# PG14__POWER_CONTROL.net
KiCad netlist of a schematic drawn in Altium Designer
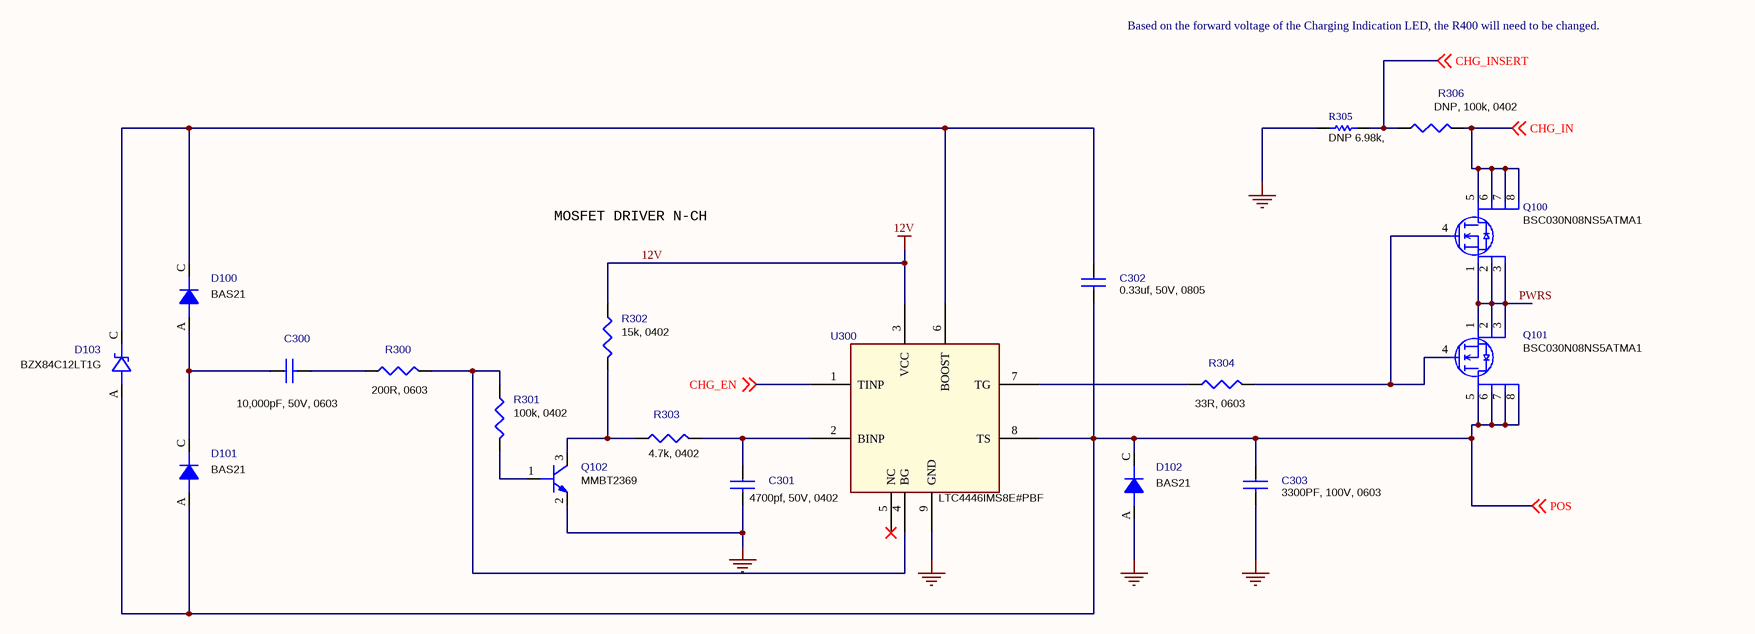
[diagram p0: PG14_ POWER CONTROL.SchDoc]

(export (version "E")
  (design (tool "Eeschema 10.0.6"))
  (components
    (comp (ref "C300")
      (value "10,000pF, 50V, 0603")
      (footprint "C0603")
      (description "CAP CER 10000PF 50V X7R 0603")
      (fields
        (field (name "MANUFACTURER") "TDK")
        (field (name "MANUFACTURER PART NUMBER") "CGA3E2X7R1H103K080AE")
      )
      (libsource (lib "*") (part "CAP-Generic-0603"))
    )
    (comp (ref "C301")
      (value "4700pf, 50V, 0402")
      (footprint "C0402")
      (description "CAP CER 4700PF 50V X7R 0402")
      (fields
        (field (name "MANUFACTURER") "TDK")
        (field (name "MANUFACTURER PART NUMBER") "CGA2B2X7R1H472K050BE")
      )
      (libsource (lib "*") (part "CAP-Generic-0402"))
    )
    (comp (ref "C302")
      (value "0.33uf, 50V, 0805")
      (footprint "C0805")
      (description "CAP CER 0.33UF 50V X7R 0805")
      (fields
        (field (name "MANUFACTURER") "KEMET")
        (field (name "MANUFACTURER PART NUMBER") "C0805X334K5RACAUTO")
      )
      (libsource (lib "*") (part "CAP-Generic-0603"))
    )
    (comp (ref "C303")
      (value "3300PF, 100V, 0603")
      (footprint "C0603")
      (description "CAP CER 3300PF 100V X7R 0603")
      (fields
        (field (name "MANUFACTURER") "Murata")
        (field (name "MANUFACTURER PART NUMBER") "GCJ188R72A332KA01D")
      )
      (libsource (lib "*") (part "CAP-Generic-0402"))
    )
    (comp (ref "D100")
      (value "BAS21")
      (footprint "BAS21")
      (description "DIODE GEN PURP 250V 200MA SOT23")
      (fields (field (name "MANUFACTURER") "Vishay") (field (name "MANUFACTURER PART NUMBER") "BAS21-HE3-08"))
      (libsource (lib "*") (part "DIO-GENERIC"))
    )
    (comp (ref "D101")
      (value "BAS21")
      (footprint "BAS21")
      (description "DIODE GEN PURP 250V 200MA SOT23")
      (fields (field (name "MANUFACTURER") "Vishay") (field (name "MANUFACTURER PART NUMBER") "BAS21-HE3-08"))
      (libsource (lib "*") (part "DIO-GENERIC"))
    )
    (comp (ref "D102")
      (value "BAS21")
      (footprint "BAS21")
      (description "DIODE GEN PURP 250V 200MA SOT23")
      (fields (field (name "MANUFACTURER") "Vishay") (field (name "MANUFACTURER PART NUMBER") "BAS21-HE3-08"))
      (libsource (lib "*") (part "DIO-GENERIC"))
    )
    (comp (ref "D103")
      (value "BZX84C12LT1G")
      (footprint "SOT23-3")
      (description "DIODE ZENER 12V 225MW SOT23-3")
      (fields (field (name "MANUFACTURER") "ON Semiconductor") (field (name "TOLERANCE") "5%"))
      (libsource (lib "*") (part "DIO-ZENER-GENERIC"))
    )
    (comp (ref "Q100")
      (value "BSC030N08NS5ATMA1")
      (footprint "8TDSON")
      (description "MOSFET N-CH 80V 100A 8TDSON")
      (fields (field (name "MANUFACTURER") "Infineon"))
      (libsource (lib "M2_V8_BMU_V1.0") (part "BSC030N08NS5ATMA1"))
    )
    (comp (ref "Q101")
      (value "BSC030N08NS5ATMA1")
      (footprint "8TDSON")
      (description "MOSFET N-CH 80V 100A 8TDSON")
      (fields (field (name "MANUFACTURER") "Infineon"))
      (libsource (lib "M2_V8_BMU_V1.0") (part "BSC030N08NS5ATMA1"))
    )
    (comp (ref "Q102")
      (value "MMBT2369")
      (footprint "SOT-23-3")
      (description "TRANS NPN 15V 0.2A SOT-23")
      (fields
        (field (name "MANUFACTURER") "ON Semiconductor / Fairchild")
        (field (name "MANUFACTURER PART NUMBER") "MMBT2369A")
      )
      (libsource (lib "*") (part "Trans-Generic_4"))
    )
    (comp (ref "R300")
      (value "200R, 0603")
      (footprint "R0603")
      (description "RES SMD 200 OHM 1% 1/10W 0603")
      (fields
        (field (name "MANUFACTURER") "Yageo")
        (field (name "MANUFACTURER PART NUMBER") "AC0603FR-07200RL")
      )
      (libsource (lib "*") (part "R-Generic-0603"))
    )
    (comp (ref "R301")
      (value "100k, 0402")
      (footprint "R0402")
      (description "RES SMD 100K OHM 1% 1/16W 0402")
      (fields
        (field (name "MANUFACTURER") "Yageo")
        (field (name "MANUFACTURER PART NUMBER") "RC0402FR-07100KL")
      )
      (libsource (lib "*") (part "R-Generic-0402"))
    )
    (comp (ref "R302")
      (value "15k, 0402")
      (footprint "R0402")
      (description "RES SMD 15K OHM 1% 1/16W 0402")
      (fields
        (field (name "MANUFACTURER") "Yageo")
        (field (name "MANUFACTURER PART NUMBER") "RC0402FR-0715KL")
      )
      (libsource (lib "*") (part "R-Generic-0402"))
    )
    (comp (ref "R303")
      (value "4.7k, 0402")
      (footprint "R0402")
      (description "RES SMD 4.7K OHM 1% 1/16W 0402")
      (fields
        (field (name "MANUFACTURER") "Yageo")
        (field (name "MANUFACTURER PART NUMBER") "RC0402FR-074K7L")
      )
      (libsource (lib "*") (part "R-Generic-0402"))
    )
    (comp (ref "R304")
      (value "33R, 0603")
      (footprint "R0603")
      (description "RES SMD 33 OHM 1% 1/10W 0603")
      (fields
        (field (name "MANUFACTURER") "Yageo")
        (field (name "MANUFACTURER PART NUMBER") "AC0603FR-0733RL")
      )
      (libsource (lib "*") (part "R-Generic-0603"))
    )
    (comp (ref "R305")
      (value "DNP 6.98k,")
      (footprint "R0402")
      (description "Resistor")
      (fields (field (name "PUBLISHER") "Altium Limited"))
      (libsource (lib "Miscellaneous Devices") (part "Res1"))
    )
    (comp (ref "R306")
      (value "DNP, 100k, 0402")
      (footprint "R0402")
      (description "RES SMD 100K OHM 1% 1/16W 0402")
      (fields
        (field (name "MANUFACTURER") "Yageo")
        (field (name "MANUFACTURER PART NUMBER") "RC0402FR-07100KL")
      )
      (libsource (lib "*") (part "R-Generic-0402"))
    )
    (comp (ref "U300")
      (value "LTC4446IMS8E#PBF")
      (footprint "8-MSOP")
      (description "IC MOSFET DRIVER N-CH 8-MSOP")
      (fields
        (field (name "MANUFACTURER") "Analog Devices / Linear Technology")
        (field (name "TOLERANCE") "10%")
      )
      (libsource (lib "*") (part "IC-LTC4446IMS8EPBF-700-510"))
    )
  )
  (nets
    (net (code "1") (name "/PWRS") (class "Default")
      (node (ref "Q100") (pin "1") (pinfunction "S1_1") (pintype "bidirectional"))
      (node (ref "Q100") (pin "2") (pinfunction "S2_2") (pintype "bidirectional"))
      (node (ref "Q100") (pin "3") (pinfunction "S3_3") (pintype "bidirectional"))
      (node (ref "Q101") (pin "1") (pinfunction "S1_1") (pintype "bidirectional"))
      (node (ref "Q101") (pin "2") (pinfunction "S2_2") (pintype "bidirectional"))
      (node (ref "Q101") (pin "3") (pinfunction "S3_3") (pintype "bidirectional"))
    )
    (net (code "2") (name "12V") (class "Default")
      (node (ref "R302") (pin "1") (pinfunction "1_1") (pintype "passive"))
      (node (ref "U300") (pin "3") (pinfunction "VCC_3") (pintype "passive"))
    )
    (net (code "3") (name "CHG_EN") (class "Default")
      (node (ref "U300") (pin "1") (pinfunction "TINP_1") (pintype "passive"))
    )
    (net (code "4") (name "CHG_IN") (class "Default")
      (node (ref "Q100") (pin "5") (pinfunction "D1_5") (pintype "bidirectional"))
      (node (ref "Q100") (pin "6") (pinfunction "D2_6") (pintype "bidirectional"))
      (node (ref "Q100") (pin "7") (pinfunction "D3_7") (pintype "bidirectional"))
      (node (ref "Q100") (pin "8") (pinfunction "D4_8") (pintype "bidirectional"))
      (node (ref "R306") (pin "2") (pinfunction "2_2") (pintype "passive"))
    )
    (net (code "5") (name "CHG_INSERT") (class "Default")
      (node (ref "R305") (pin "2") (pinfunction "2_2") (pintype "passive"))
      (node (ref "R306") (pin "1") (pinfunction "1_1") (pintype "passive"))
    )
    (net (code "6") (name "GND") (class "Default")
      (node (ref "C301") (pin "2") (pinfunction "2_2") (pintype "passive"))
      (node (ref "C303") (pin "2") (pinfunction "2_2") (pintype "passive"))
      (node (ref "D102") (pin "A") (pinfunction "ANODE_A") (pintype "passive"))
      (node (ref "Q102") (pin "2") (pinfunction "E_2") (pintype "passive"))
      (node (ref "R305") (pin "1") (pinfunction "1_1") (pintype "passive"))
      (node (ref "U300") (pin "9") (pinfunction "GND_9") (pintype "passive"))
    )
    (net (code "7") (name "Net-(C300-Pad2)") (class "Default")
      (node (ref "C300") (pin "2") (pinfunction "2_2") (pintype "passive"))
      (node (ref "R300") (pin "1") (pinfunction "1_1") (pintype "passive"))
    )
    (net (code "8") (name "Net-(D100-ANODE)") (class "Default")
      (node (ref "C300") (pin "1") (pinfunction "1_1") (pintype "passive"))
      (node (ref "D100") (pin "A") (pinfunction "ANODE_A") (pintype "passive"))
      (node (ref "D101") (pin "C") (pinfunction "CATHODE_C") (pintype "passive"))
    )
    (net (code "9") (name "Net-(D100-CATHODE)") (class "Default")
      (node (ref "C302") (pin "1") (pinfunction "1_1") (pintype "passive"))
      (node (ref "D100") (pin "C") (pinfunction "CATHODE_C") (pintype "passive"))
      (node (ref "D103") (pin "C") (pinfunction "CATHODE_C") (pintype "passive"))
      (node (ref "U300") (pin "6") (pinfunction "BOOST_6") (pintype "passive"))
    )
    (net (code "10") (name "Net-(Q100-G)") (class "Default")
      (node (ref "Q100") (pin "4") (pinfunction "G_4") (pintype "input"))
      (node (ref "Q101") (pin "4") (pinfunction "G_4") (pintype "input"))
      (node (ref "R304") (pin "2") (pinfunction "2_2") (pintype "passive"))
    )
    (net (code "11") (name "Net-(Q102-B)") (class "Default")
      (node (ref "Q102") (pin "1") (pinfunction "B_1") (pintype "passive"))
      (node (ref "R301") (pin "2") (pinfunction "2_2") (pintype "passive"))
    )
    (net (code "12") (name "Net-(Q102-C)") (class "Default")
      (node (ref "Q102") (pin "3") (pinfunction "C_3") (pintype "passive"))
      (node (ref "R302") (pin "2") (pinfunction "2_2") (pintype "passive"))
      (node (ref "R303") (pin "1") (pinfunction "1_1") (pintype "passive"))
    )
    (net (code "13") (name "Net-(U300-BG)") (class "Default")
      (node (ref "R300") (pin "2") (pinfunction "2_2") (pintype "passive"))
      (node (ref "R301") (pin "1") (pinfunction "1_1") (pintype "passive"))
      (node (ref "U300") (pin "4") (pinfunction "BG_4") (pintype "passive"))
    )
    (net (code "14") (name "Net-(U300-BINP)") (class "Default")
      (node (ref "C301") (pin "1") (pinfunction "1_1") (pintype "passive"))
      (node (ref "R303") (pin "2") (pinfunction "2_2") (pintype "passive"))
      (node (ref "U300") (pin "2") (pinfunction "BINP_2") (pintype "passive"))
    )
    (net (code "15") (name "Net-(U300-TG)") (class "Default")
      (node (ref "R304") (pin "1") (pinfunction "1_1") (pintype "passive"))
      (node (ref "U300") (pin "7") (pinfunction "TG_7") (pintype "passive"))
    )
    (net (code "16") (name "POS") (class "Default")
      (node (ref "C302") (pin "2") (pinfunction "2_2") (pintype "passive"))
      (node (ref "C303") (pin "1") (pinfunction "1_1") (pintype "passive"))
      (node (ref "D101") (pin "A") (pinfunction "ANODE_A") (pintype "passive"))
      (node (ref "D102") (pin "C") (pinfunction "CATHODE_C") (pintype "passive"))
      (node (ref "D103") (pin "A") (pinfunction "ANODE_A") (pintype "passive"))
      (node (ref "Q101") (pin "5") (pinfunction "D1_5") (pintype "bidirectional"))
      (node (ref "Q101") (pin "6") (pinfunction "D2_6") (pintype "bidirectional"))
      (node (ref "Q101") (pin "7") (pinfunction "D3_7") (pintype "bidirectional"))
      (node (ref "Q101") (pin "8") (pinfunction "D4_8") (pintype "bidirectional"))
      (node (ref "U300") (pin "8") (pinfunction "TS_8") (pintype "passive"))
    )
    (net (code "17") (name "unconnected-(U300-NC-Pad5)") (class "Default")
      (node (ref "U300") (pin "5") (pinfunction "NC_5") (pintype "passive+no_connect"))
    )
  )
)
